# scHnRk_5.net
KiCad netlist of a schematic drawn in EAGLE
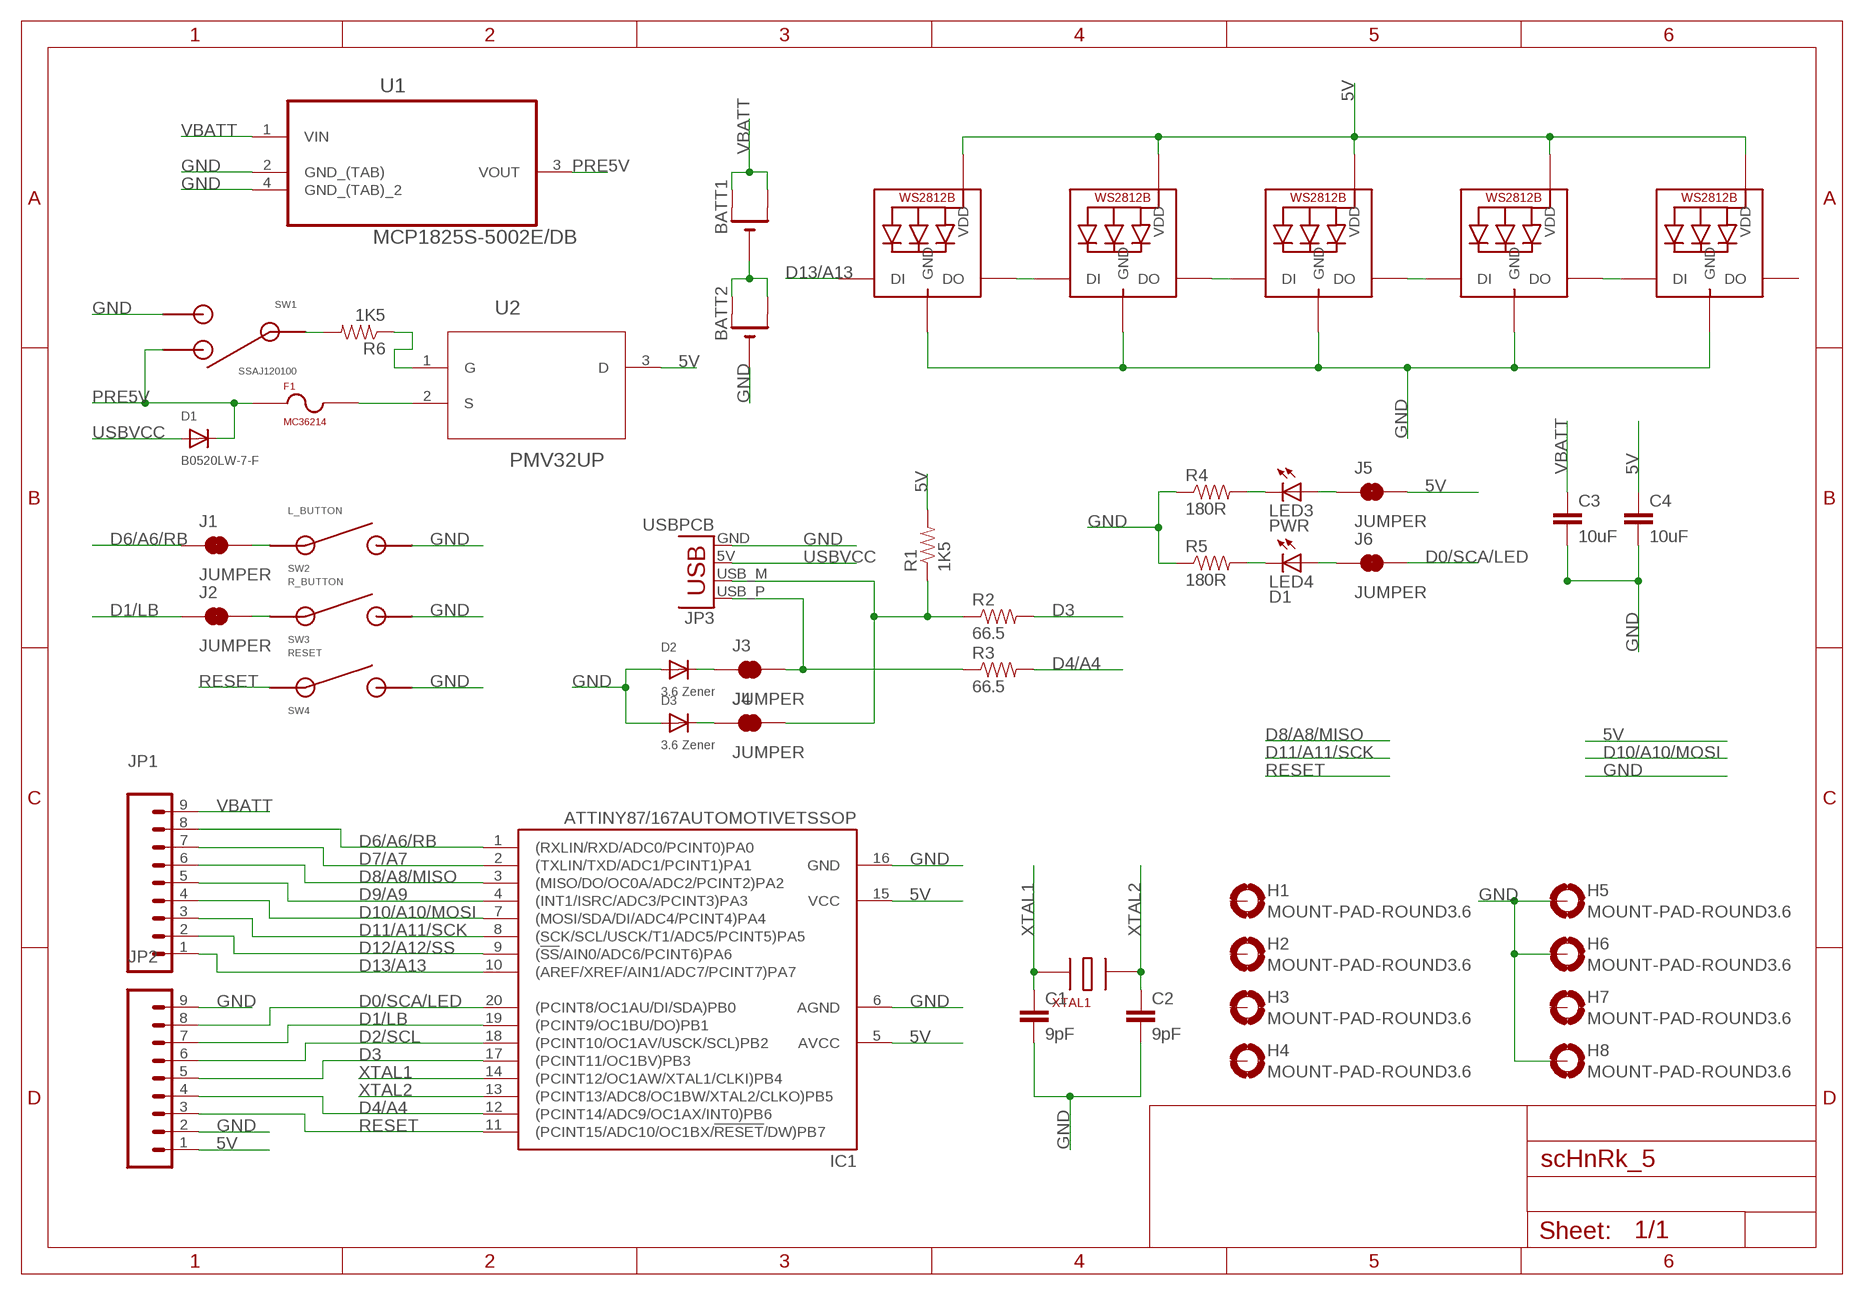
[diagram p0: schematic, sheet 1]

(export (version "E")
  (design (tool "Eeschema 10.0.6"))
  (components
    (comp (ref "BATT1")
      (value "CR2032SMT")
      (footprint "eagle-import:CR2032-SMD")
      (libsource (lib "eagle-import") (part "CR2032SMT"))
    )
    (comp (ref "BATT2")
      (value "CR2032SMT")
      (footprint "eagle-import:CR2032-SMD")
      (libsource (lib "eagle-import") (part "CR2032SMT"))
    )
    (comp (ref "C1")
      (value "9pF")
      (footprint "eagle-import:0603-CAP")
      (libsource (lib "eagle-import") (part "CAP0603-CAP"))
    )
    (comp (ref "C2")
      (value "9pF")
      (footprint "eagle-import:0603-CAP")
      (libsource (lib "eagle-import") (part "CAP0603-CAP"))
    )
    (comp (ref "C3")
      (value "10uF")
      (footprint "eagle-import:0805")
      (libsource (lib "eagle-import") (part "CAP0805"))
    )
    (comp (ref "C4")
      (value "10uF")
      (footprint "eagle-import:0805")
      (libsource (lib "eagle-import") (part "CAP0805"))
    )
    (comp (ref "D1")
      (value "B0520LW-7-F")
      (footprint "eagle-import:SOD-123")
      (libsource (lib "eagle-import") (part "DIODESOD-123"))
    )
    (comp (ref "D2")
      (value "3.6 Zener")
      (footprint "eagle-import:SOD-523")
      (libsource (lib "eagle-import") (part "DIODESOD-523"))
    )
    (comp (ref "D3")
      (value "3.6 Zener")
      (footprint "eagle-import:SOD-523")
      (libsource (lib "eagle-import") (part "DIODESOD-523"))
    )
    (comp (ref "F1")
      (value "MC36214")
      (footprint "eagle-import:MC36214")
      (libsource (lib "eagle-import") (part "MC36214"))
    )
    (comp (ref "H1")
      (value "MOUNT-PAD-ROUND3.6")
      (footprint "eagle-import:3,6-PAD")
      (libsource (lib "eagle-import") (part "MOUNT-PAD-ROUND3.6"))
    )
    (comp (ref "H2")
      (value "MOUNT-PAD-ROUND3.6")
      (footprint "eagle-import:3,6-PAD")
      (libsource (lib "eagle-import") (part "MOUNT-PAD-ROUND3.6"))
    )
    (comp (ref "H3")
      (value "MOUNT-PAD-ROUND3.6")
      (footprint "eagle-import:3,6-PAD")
      (libsource (lib "eagle-import") (part "MOUNT-PAD-ROUND3.6"))
    )
    (comp (ref "H4")
      (value "MOUNT-PAD-ROUND3.6")
      (footprint "eagle-import:3,6-PAD")
      (libsource (lib "eagle-import") (part "MOUNT-PAD-ROUND3.6"))
    )
    (comp (ref "H5")
      (value "MOUNT-PAD-ROUND3.6")
      (footprint "eagle-import:3,6-PAD")
      (libsource (lib "eagle-import") (part "MOUNT-PAD-ROUND3.6"))
    )
    (comp (ref "H6")
      (value "MOUNT-PAD-ROUND3.6")
      (footprint "eagle-import:3,6-PAD")
      (libsource (lib "eagle-import") (part "MOUNT-PAD-ROUND3.6"))
    )
    (comp (ref "H7")
      (value "MOUNT-PAD-ROUND3.6")
      (footprint "eagle-import:3,6-PAD")
      (libsource (lib "eagle-import") (part "MOUNT-PAD-ROUND3.6"))
    )
    (comp (ref "H8")
      (value "MOUNT-PAD-ROUND3.6")
      (footprint "eagle-import:3,6-PAD")
      (libsource (lib "eagle-import") (part "MOUNT-PAD-ROUND3.6"))
    )
    (comp (ref "IC1")
      (value "ATTINY87/167AUTOMOTIVETSSOP")
      (footprint "eagle-import:TSSOP20")
      (libsource (lib "eagle-import") (part "ATTINY87/167AUTOMOTIVETSSOP"))
    )
    (comp (ref "J1")
      (value "JUMPER")
      (footprint "eagle-import:PAD-JUMPER-2-NC_BY_TRACE_YES_SILK")
      (libsource (lib "eagle-import") (part "JUMPER-PAD-2-NC_BY_TRACE"))
    )
    (comp (ref "J2")
      (value "JUMPER")
      (footprint "eagle-import:PAD-JUMPER-2-NC_BY_TRACE_YES_SILK")
      (libsource (lib "eagle-import") (part "JUMPER-PAD-2-NC_BY_TRACE"))
    )
    (comp (ref "J3")
      (value "JUMPER")
      (footprint "eagle-import:PAD-JUMPER-2-NC_BY_TRACE_YES_SILK")
      (libsource (lib "eagle-import") (part "JUMPER-PAD-2-NC_BY_TRACE"))
    )
    (comp (ref "J4")
      (value "JUMPER")
      (footprint "eagle-import:PAD-JUMPER-2-NC_BY_TRACE_YES_SILK")
      (libsource (lib "eagle-import") (part "JUMPER-PAD-2-NC_BY_TRACE"))
    )
    (comp (ref "J5")
      (value "JUMPER")
      (footprint "eagle-import:PAD-JUMPER-2-NC_BY_TRACE_YES_SILK")
      (libsource (lib "eagle-import") (part "JUMPER-PAD-2-NC_BY_TRACE"))
    )
    (comp (ref "J6")
      (value "JUMPER")
      (footprint "eagle-import:PAD-JUMPER-2-NC_BY_TRACE_YES_SILK")
      (libsource (lib "eagle-import") (part "JUMPER-PAD-2-NC_BY_TRACE"))
    )
    (comp (ref "JP1")
      (value "M09")
      (footprint "eagle-import:1X09")
      (libsource (lib "eagle-import") (part "M09"))
    )
    (comp (ref "JP2")
      (value "M09")
      (footprint "eagle-import:1X09")
      (libsource (lib "eagle-import") (part "M09"))
    )
    (comp (ref "JP3")
      (value "USBPCB")
      (footprint "eagle-import:USB-A-PCB")
      (libsource (lib "eagle-import") (part "USBPCB"))
    )
    (comp (ref "LED1")
      (value "WS2812B5050")
      (footprint "eagle-import:WS2812B")
      (libsource (lib "eagle-import") (part "WS2812B5050"))
    )
    (comp (ref "LED2")
      (value "WS2812B5050")
      (footprint "eagle-import:WS2812B")
      (libsource (lib "eagle-import") (part "WS2812B5050"))
    )
    (comp (ref "LED3")
      (value "PWR")
      (footprint "eagle-import:CHIPLED_0603")
      (libsource (lib "eagle-import") (part "LEDCHIPLED_0603"))
    )
    (comp (ref "LED4")
      (value "D1")
      (footprint "eagle-import:CHIPLED_0603")
      (libsource (lib "eagle-import") (part "LEDCHIPLED_0603"))
    )
    (comp (ref "LED5")
      (value "WS2812B5050")
      (footprint "eagle-import:WS2812B")
      (libsource (lib "eagle-import") (part "WS2812B5050"))
    )
    (comp (ref "LED6")
      (value "WS2812B5050")
      (footprint "eagle-import:WS2812B")
      (libsource (lib "eagle-import") (part "WS2812B5050"))
    )
    (comp (ref "LED7")
      (value "WS2812B5050")
      (footprint "eagle-import:WS2812B")
      (libsource (lib "eagle-import") (part "WS2812B5050"))
    )
    (comp (ref "R1")
      (value "1K5")
      (footprint "eagle-import:0805")
      (libsource (lib "eagle-import") (part "RESISTOR0805-RES"))
    )
    (comp (ref "R2")
      (value "66.5")
      (footprint "eagle-import:0603-RES")
      (libsource (lib "eagle-import") (part "RESISTOR0603-RES"))
    )
    (comp (ref "R3")
      (value "66.5")
      (footprint "eagle-import:0603-RES")
      (libsource (lib "eagle-import") (part "RESISTOR0603-RES"))
    )
    (comp (ref "R4")
      (value "180R")
      (footprint "eagle-import:0805")
      (libsource (lib "eagle-import") (part "RESISTOR0805-RES"))
    )
    (comp (ref "R5")
      (value "180R")
      (footprint "eagle-import:0805")
      (libsource (lib "eagle-import") (part "RESISTOR0805-RES"))
    )
    (comp (ref "R6")
      (value "1K5")
      (footprint "eagle-import:0805")
      (libsource (lib "eagle-import") (part "RESISTOR0805-RES"))
    )
    (comp (ref "SW1")
      (value "SSAJ120100")
      (footprint "eagle-import:SSAJ120100")
      (libsource (lib "eagle-import") (part "SSAJ120100"))
    )
    (comp (ref "SW2")
      (value "L_BUTTON")
      (footprint "eagle-import:SKRBAGE010")
      (libsource (lib "eagle-import") (part "SKRBAGE010"))
    )
    (comp (ref "SW3")
      (value "R_BUTTON")
      (footprint "eagle-import:SKRBAGE010")
      (libsource (lib "eagle-import") (part "SKRBAGE010"))
    )
    (comp (ref "SW4")
      (value "RESET")
      (footprint "eagle-import:SKRBAGE010")
      (libsource (lib "eagle-import") (part "SKRBAGE010"))
    )
    (comp (ref "U1")
      (value "MCP1825S-5002E/DB")
      (footprint "eagle-import:SOT230P700X180-4N")
      (libsource (lib "eagle-import") (part "MCP1825S-5002E/DB"))
    )
    (comp (ref "U2")
      (value "PMV32UP")
      (footprint "eagle-import:SOT95P230X110-3N")
      (libsource (lib "eagle-import") (part "PMV32UP"))
    )
    (comp (ref "XTAL1")
      (value "16MHZ-2467444")
      (footprint "eagle-import:16MHZ-2467444")
      (libsource (lib "eagle-import") (part "16MHZ-2467444"))
    )
  )
  (nets
    (net (code "1") (name "/5V") (class "Default")
      (node (ref "C4") (pin "1") (pinfunction "1_1") (pintype "passive"))
      (node (ref "IC1") (pin "15") (pinfunction "VCC_15") (pintype "power_in"))
      (node (ref "IC1") (pin "5") (pinfunction "AVCC_5") (pintype "bidirectional"))
      (node (ref "J5") (pin "2") (pinfunction "2_2") (pintype "passive"))
      (node (ref "JP2") (pin "1") (pinfunction "1_1") (pintype "passive"))
      (node (ref "LED1") (pin "1-VDD") (pinfunction "VDD_1-VDD") (pintype "power_in"))
      (node (ref "LED2") (pin "1-VDD") (pinfunction "VDD_1-VDD") (pintype "power_in"))
      (node (ref "LED5") (pin "1-VDD") (pinfunction "VDD_1-VDD") (pintype "power_in"))
      (node (ref "LED6") (pin "1-VDD") (pinfunction "VDD_1-VDD") (pintype "power_in"))
      (node (ref "LED7") (pin "1-VDD") (pinfunction "VDD_1-VDD") (pintype "power_in"))
      (node (ref "R1") (pin "2") (pinfunction "2_2") (pintype "passive"))
      (node (ref "U2") (pin "3") (pinfunction "D_3") (pintype "passive"))
    )
    (net (code "2") (name "/D0{slash}SCA{slash}LED") (class "Default")
      (node (ref "IC1") (pin "20") (pinfunction "(PCINT8/OC1AU/DI/SDA)PB0_20") (pintype "bidirectional"))
      (node (ref "J6") (pin "2") (pinfunction "2_2") (pintype "passive"))
      (node (ref "JP2") (pin "8") (pinfunction "8_8") (pintype "passive"))
    )
    (net (code "3") (name "/D1{slash}LB") (class "Default")
      (node (ref "IC1") (pin "19") (pinfunction "(PCINT9/OC1BU/DO)PB1_19") (pintype "bidirectional"))
      (node (ref "J2") (pin "1") (pinfunction "1_1") (pintype "passive"))
      (node (ref "JP2") (pin "7") (pinfunction "7_7") (pintype "passive"))
    )
    (net (code "4") (name "/D2{slash}SCL") (class "Default")
      (node (ref "IC1") (pin "18") (pinfunction "(PCINT10/OC1AV/USCK/SCL)PB2_18") (pintype "bidirectional"))
      (node (ref "JP2") (pin "6") (pinfunction "6_6") (pintype "passive"))
    )
    (net (code "5") (name "/D3") (class "Default")
      (node (ref "IC1") (pin "17") (pinfunction "(PCINT11/OC1BV)PB3_17") (pintype "bidirectional"))
      (node (ref "JP2") (pin "5") (pinfunction "5_5") (pintype "passive"))
      (node (ref "R2") (pin "2") (pinfunction "2_2") (pintype "passive"))
    )
    (net (code "6") (name "/D4{slash}A4") (class "Default")
      (node (ref "IC1") (pin "12") (pinfunction "(PCINT14/ADC9/OC1AX/INT0)PB6_12") (pintype "bidirectional"))
      (node (ref "JP2") (pin "4") (pinfunction "4_4") (pintype "passive"))
      (node (ref "R3") (pin "2") (pinfunction "2_2") (pintype "passive"))
    )
    (net (code "7") (name "/D6{slash}A6{slash}RB") (class "Default")
      (node (ref "IC1") (pin "1") (pinfunction "(RXLIN/RXD/ADC0/PCINT0)PA0_1") (pintype "bidirectional"))
      (node (ref "J1") (pin "1") (pinfunction "1_1") (pintype "passive"))
      (node (ref "JP1") (pin "8") (pinfunction "8_8") (pintype "passive"))
    )
    (net (code "8") (name "/D7{slash}A7") (class "Default")
      (node (ref "IC1") (pin "2") (pinfunction "(TXLIN/TXD/ADC1/PCINT1)PA1_2") (pintype "bidirectional"))
      (node (ref "JP1") (pin "7") (pinfunction "7_7") (pintype "passive"))
    )
    (net (code "9") (name "/D8{slash}A8{slash}MISO") (class "Default")
      (node (ref "IC1") (pin "3") (pinfunction "(MISO/DO/OC0A/ADC2/PCINT2)PA2_3") (pintype "bidirectional"))
      (node (ref "JP1") (pin "6") (pinfunction "6_6") (pintype "passive"))
    )
    (net (code "10") (name "/D9{slash}A9") (class "Default")
      (node (ref "IC1") (pin "4") (pinfunction "(INT1/ISRC/ADC3/PCINT3)PA3_4") (pintype "bidirectional"))
      (node (ref "JP1") (pin "5") (pinfunction "5_5") (pintype "passive"))
    )
    (net (code "11") (name "/D10{slash}A10{slash}MOSI") (class "Default")
      (node (ref "IC1") (pin "7") (pinfunction "(MOSI/SDA/DI/ADC4/PCINT4)PA4_7") (pintype "bidirectional"))
      (node (ref "JP1") (pin "4") (pinfunction "4_4") (pintype "passive"))
    )
    (net (code "12") (name "/D11{slash}A11{slash}SCK") (class "Default")
      (node (ref "IC1") (pin "8") (pinfunction "(SCK/SCL/USCK/T1/ADC5/PCINT5)PA5_8") (pintype "bidirectional"))
      (node (ref "JP1") (pin "3") (pinfunction "3_3") (pintype "passive"))
    )
    (net (code "13") (name "/D12{slash}A12{slash}SS") (class "Default")
      (node (ref "IC1") (pin "9") (pinfunction "(~{SS}/AIN0/ADC6/PCINT6)PA6_9") (pintype "bidirectional"))
      (node (ref "JP1") (pin "2") (pinfunction "2_2") (pintype "passive"))
    )
    (net (code "14") (name "/D13{slash}A13") (class "Default")
      (node (ref "IC1") (pin "10") (pinfunction "(AREF/XREF/AIN1/ADC7/PCINT7)PA7_10") (pintype "bidirectional"))
      (node (ref "JP1") (pin "1") (pinfunction "1_1") (pintype "passive"))
      (node (ref "LED1") (pin "4-DIN") (pinfunction "DI_4-DIN") (pintype "input"))
    )
    (net (code "15") (name "/GND") (class "Default")
      (node (ref "BATT2") (pin "-") (pinfunction "-_-") (pintype "passive"))
      (node (ref "C1") (pin "2") (pinfunction "2_2") (pintype "passive"))
      (node (ref "C2") (pin "2") (pinfunction "2_2") (pintype "passive"))
      (node (ref "C3") (pin "2") (pinfunction "2_2") (pintype "passive"))
      (node (ref "C4") (pin "2") (pinfunction "2_2") (pintype "passive"))
      (node (ref "D2") (pin "A") (pinfunction "A_A") (pintype "passive"))
      (node (ref "D3") (pin "A") (pinfunction "A_A") (pintype "passive"))
      (node (ref "H5") (pin "B3,6") (pinfunction "MOUNT_B3,6") (pintype "passive"))
      (node (ref "H6") (pin "B3,6") (pinfunction "MOUNT_B3,6") (pintype "passive"))
      (node (ref "H8") (pin "B3,6") (pinfunction "MOUNT_B3,6") (pintype "passive"))
      (node (ref "IC1") (pin "16") (pinfunction "GND_16") (pintype "power_in"))
      (node (ref "IC1") (pin "6") (pinfunction "AGND_6") (pintype "bidirectional"))
      (node (ref "JP2") (pin "2") (pinfunction "2_2") (pintype "passive"))
      (node (ref "JP2") (pin "9") (pinfunction "9_9") (pintype "passive"))
      (node (ref "JP3") (pin "GND") (pinfunction "GND_GND") (pintype "bidirectional"))
      (node (ref "LED1") (pin "3-GND") (pinfunction "GND_3-GND") (pintype "power_in"))
      (node (ref "LED2") (pin "3-GND") (pinfunction "GND_3-GND") (pintype "power_in"))
      (node (ref "LED5") (pin "3-GND") (pinfunction "GND_3-GND") (pintype "power_in"))
      (node (ref "LED6") (pin "3-GND") (pinfunction "GND_3-GND") (pintype "power_in"))
      (node (ref "LED7") (pin "3-GND") (pinfunction "GND_3-GND") (pintype "power_in"))
      (node (ref "R4") (pin "1") (pinfunction "1_1") (pintype "passive"))
      (node (ref "R5") (pin "1") (pinfunction "1_1") (pintype "passive"))
      (node (ref "SW1") (pin "P$2") (pinfunction "P$2_P$2") (pintype "bidirectional"))
      (node (ref "SW2") (pin "P$2") (pinfunction "P$2_P$2") (pintype "bidirectional"))
      (node (ref "SW2") (pin "P$4") (pinfunction "P$2_P$4") (pintype "bidirectional"))
      (node (ref "SW3") (pin "P$2") (pinfunction "P$2_P$2") (pintype "bidirectional"))
      (node (ref "SW3") (pin "P$4") (pinfunction "P$2_P$4") (pintype "bidirectional"))
      (node (ref "SW4") (pin "P$2") (pinfunction "P$2_P$2") (pintype "bidirectional"))
      (node (ref "SW4") (pin "P$4") (pinfunction "P$2_P$4") (pintype "bidirectional"))
      (node (ref "U1") (pin "2") (pinfunction "GND_(TAB)_2") (pintype "passive"))
      (node (ref "U1") (pin "4") (pinfunction "GND_(TAB)_2_4") (pintype "passive"))
    )
    (net (code "16") (name "/PRE5V") (class "Default")
      (node (ref "D1") (pin "C") (pinfunction "C_C") (pintype "passive"))
      (node (ref "F1") (pin "P$1") (pinfunction "P$1_P$1") (pintype "bidirectional"))
      (node (ref "SW1") (pin "P$1") (pinfunction "P$1_P$1") (pintype "bidirectional"))
      (node (ref "U1") (pin "3") (pinfunction "VOUT_3") (pintype "output"))
    )
    (net (code "17") (name "/RESET") (class "Default")
      (node (ref "IC1") (pin "11") (pinfunction "(PCINT15/ADC10/OC1BX/~{RESET}/DW)PB7_11") (pintype "bidirectional"))
      (node (ref "JP2") (pin "3") (pinfunction "3_3") (pintype "passive"))
      (node (ref "SW4") (pin "P$1") (pinfunction "P$1_P$1") (pintype "bidirectional"))
      (node (ref "SW4") (pin "P$3") (pinfunction "P$1_P$3") (pintype "bidirectional"))
    )
    (net (code "18") (name "/USBVCC") (class "Default")
      (node (ref "D1") (pin "A") (pinfunction "A_A") (pintype "passive"))
      (node (ref "JP3") (pin "5V") (pinfunction "VBUS_5V") (pintype "bidirectional"))
    )
    (net (code "19") (name "/VBATT") (class "Default")
      (node (ref "BATT1") (pin "+$1") (pinfunction "+_+$1") (pintype "passive"))
      (node (ref "BATT1") (pin "+$2") (pinfunction "+1_+$2") (pintype "passive"))
      (node (ref "C3") (pin "1") (pinfunction "1_1") (pintype "passive"))
      (node (ref "JP1") (pin "9") (pinfunction "9_9") (pintype "passive"))
      (node (ref "U1") (pin "1") (pinfunction "VIN_1") (pintype "input"))
    )
    (net (code "20") (name "/XTAL1") (class "Default")
      (node (ref "C1") (pin "1") (pinfunction "1_1") (pintype "passive"))
      (node (ref "IC1") (pin "14") (pinfunction "(PCINT12/OC1AW/XTAL1/CLKI)PB4_14") (pintype "bidirectional"))
      (node (ref "XTAL1") (pin "P$1") (pinfunction "P$1_P$1") (pintype "bidirectional"))
    )
    (net (code "21") (name "/XTAL2") (class "Default")
      (node (ref "C2") (pin "1") (pinfunction "1_1") (pintype "passive"))
      (node (ref "IC1") (pin "13") (pinfunction "(PCINT13/ADC8/OC1BW/XTAL2/CLKO)PB5_13") (pintype "bidirectional"))
      (node (ref "XTAL1") (pin "P$3") (pinfunction "P$2_P$3") (pintype "bidirectional"))
    )
    (net (code "22") (name "Net-(BATT2-+)") (class "Default")
      (node (ref "BATT1") (pin "-") (pinfunction "-_-") (pintype "passive"))
      (node (ref "BATT2") (pin "+$1") (pinfunction "+_+$1") (pintype "passive"))
      (node (ref "BATT2") (pin "+$2") (pinfunction "+1_+$2") (pintype "passive"))
    )
    (net (code "23") (name "Net-(D2-C)") (class "Default")
      (node (ref "D2") (pin "K") (pinfunction "C_K") (pintype "passive"))
      (node (ref "J3") (pin "1") (pinfunction "1_1") (pintype "passive"))
    )
    (net (code "24") (name "Net-(D3-C)") (class "Default")
      (node (ref "D3") (pin "K") (pinfunction "C_K") (pintype "passive"))
      (node (ref "J4") (pin "1") (pinfunction "1_1") (pintype "passive"))
    )
    (net (code "25") (name "Net-(J1-Pad2)") (class "Default")
      (node (ref "J1") (pin "2") (pinfunction "2_2") (pintype "passive"))
      (node (ref "SW2") (pin "P$1") (pinfunction "P$1_P$1") (pintype "bidirectional"))
      (node (ref "SW2") (pin "P$3") (pinfunction "P$1_P$3") (pintype "bidirectional"))
    )
    (net (code "26") (name "Net-(J2-Pad2)") (class "Default")
      (node (ref "J2") (pin "2") (pinfunction "2_2") (pintype "passive"))
      (node (ref "SW3") (pin "P$1") (pinfunction "P$1_P$1") (pintype "bidirectional"))
      (node (ref "SW3") (pin "P$3") (pinfunction "P$1_P$3") (pintype "bidirectional"))
    )
    (net (code "27") (name "Net-(J5-Pad1)") (class "Default")
      (node (ref "J5") (pin "1") (pinfunction "1_1") (pintype "passive"))
      (node (ref "LED3") (pin "A") (pinfunction "A_A") (pintype "passive"))
    )
    (net (code "28") (name "Net-(J6-Pad1)") (class "Default")
      (node (ref "J6") (pin "1") (pinfunction "1_1") (pintype "passive"))
      (node (ref "LED4") (pin "A") (pinfunction "A_A") (pintype "passive"))
    )
    (net (code "29") (name "Net-(JP3-D+)") (class "Default")
      (node (ref "J3") (pin "2") (pinfunction "2_2") (pintype "passive"))
      (node (ref "JP3") (pin "USB_P") (pinfunction "D+_USB_P") (pintype "bidirectional"))
      (node (ref "R3") (pin "1") (pinfunction "1_1") (pintype "passive"))
    )
    (net (code "30") (name "Net-(JP3-D-)") (class "Default")
      (node (ref "J4") (pin "2") (pinfunction "2_2") (pintype "passive"))
      (node (ref "JP3") (pin "USB_M") (pinfunction "D-_USB_M") (pintype "bidirectional"))
      (node (ref "R1") (pin "1") (pinfunction "1_1") (pintype "passive"))
      (node (ref "R2") (pin "1") (pinfunction "1_1") (pintype "passive"))
    )
    (net (code "31") (name "Net-(LED1-DO)") (class "Default")
      (node (ref "LED1") (pin "2-DOUT") (pinfunction "DO_2-DOUT") (pintype "output"))
      (node (ref "LED2") (pin "4-DIN") (pinfunction "DI_4-DIN") (pintype "input"))
    )
    (net (code "32") (name "Net-(LED2-DO)") (class "Default")
      (node (ref "LED2") (pin "2-DOUT") (pinfunction "DO_2-DOUT") (pintype "output"))
      (node (ref "LED5") (pin "4-DIN") (pinfunction "DI_4-DIN") (pintype "input"))
    )
    (net (code "33") (name "Net-(LED3-PadC)") (class "Default")
      (node (ref "LED3") (pin "C") (pinfunction "C_C") (pintype "passive"))
      (node (ref "R4") (pin "2") (pinfunction "2_2") (pintype "passive"))
    )
    (net (code "34") (name "Net-(LED4-PadC)") (class "Default")
      (node (ref "LED4") (pin "C") (pinfunction "C_C") (pintype "passive"))
      (node (ref "R5") (pin "2") (pinfunction "2_2") (pintype "passive"))
    )
    (net (code "35") (name "Net-(LED5-DO)") (class "Default")
      (node (ref "LED5") (pin "2-DOUT") (pinfunction "DO_2-DOUT") (pintype "output"))
      (node (ref "LED6") (pin "4-DIN") (pinfunction "DI_4-DIN") (pintype "input"))
    )
    (net (code "36") (name "Net-(LED6-DO)") (class "Default")
      (node (ref "LED6") (pin "2-DOUT") (pinfunction "DO_2-DOUT") (pintype "output"))
      (node (ref "LED7") (pin "4-DIN") (pinfunction "DI_4-DIN") (pintype "input"))
    )
    (net (code "37") (name "Net-(R6-Pad2)") (class "Default")
      (node (ref "R6") (pin "2") (pinfunction "2_2") (pintype "passive"))
      (node (ref "SW1") (pin "P$C") (pinfunction "P$C_P$C") (pintype "bidirectional"))
    )
    (net (code "38") (name "Net-(U2-G)") (class "Default")
      (node (ref "R6") (pin "1") (pinfunction "1_1") (pintype "passive"))
      (node (ref "U2") (pin "1") (pinfunction "G_1") (pintype "passive"))
    )
    (net (code "39") (name "Net-(U2-S)") (class "Default")
      (node (ref "F1") (pin "P$2") (pinfunction "P$2_P$2") (pintype "bidirectional"))
      (node (ref "U2") (pin "2") (pinfunction "S_2") (pintype "passive"))
    )
    (net (code "40") (name "unconnected-(H1-MOUNT-PadB3,6)") (class "Default")
      (node (ref "H1") (pin "B3,6") (pinfunction "MOUNT_B3,6") (pintype "passive"))
    )
    (net (code "41") (name "unconnected-(H2-MOUNT-PadB3,6)") (class "Default")
      (node (ref "H2") (pin "B3,6") (pinfunction "MOUNT_B3,6") (pintype "passive"))
    )
    (net (code "42") (name "unconnected-(H3-MOUNT-PadB3,6)") (class "Default")
      (node (ref "H3") (pin "B3,6") (pinfunction "MOUNT_B3,6") (pintype "passive"))
    )
    (net (code "43") (name "unconnected-(H4-MOUNT-PadB3,6)") (class "Default")
      (node (ref "H4") (pin "B3,6") (pinfunction "MOUNT_B3,6") (pintype "passive"))
    )
    (net (code "44") (name "unconnected-(H7-MOUNT-PadB3,6)") (class "Default")
      (node (ref "H7") (pin "B3,6") (pinfunction "MOUNT_B3,6") (pintype "passive"))
    )
    (net (code "45") (name "unconnected-(LED7-DO-Pad2-DOUT)") (class "Default")
      (node (ref "LED7") (pin "2-DOUT") (pinfunction "DO_2-DOUT") (pintype "output"))
    )
  )
)
